# Sheet2.net
KiCad netlist of a schematic drawn in Altium Designer
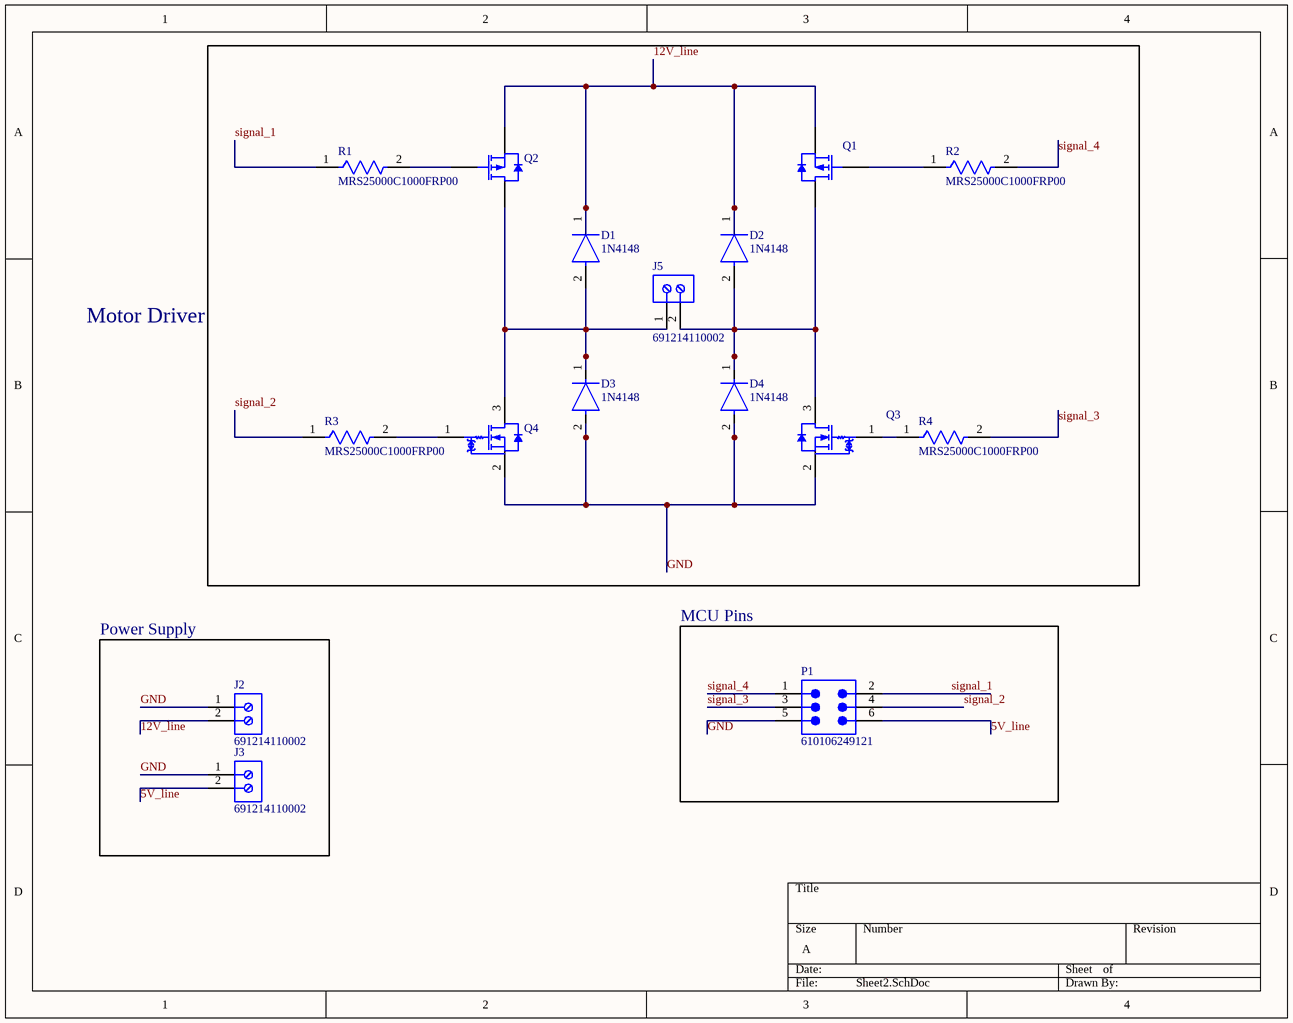
[diagram p0: Sheet2.SchDoc]

(export (version "E")
  (design (tool "Eeschema 10.0.6"))
  (components
    (comp (ref "D1")
      (value "1N4148")
      (footprint "FP-017AG-MFG")
      (description "DIODE GEN PURP 100V 200MA DO35")
      (fields (field (name "VOLTAGE") "100V"))
      (libsource (lib "Altium Content Vault") (part "d7152d700b627762746794eb795d46e"))
    )
    (comp (ref "D2")
      (value "1N4148")
      (footprint "FP-017AG-MFG")
      (description "DIODE GEN PURP 100V 200MA DO35")
      (fields (field (name "VOLTAGE") "100V"))
      (libsource (lib "Altium Content Vault") (part "d7152d700b627762746794eb795d46e"))
    )
    (comp (ref "D3")
      (value "1N4148")
      (footprint "FP-017AG-MFG")
      (description "DIODE GEN PURP 100V 200MA DO35")
      (fields (field (name "VOLTAGE") "100V"))
      (libsource (lib "Altium Content Vault") (part "d7152d700b627762746794eb795d46e"))
    )
    (comp (ref "D4")
      (value "1N4148")
      (footprint "FP-017AG-MFG")
      (description "DIODE GEN PURP 100V 200MA DO35")
      (fields (field (name "VOLTAGE") "100V"))
      (libsource (lib "Altium Content Vault") (part "d7152d700b627762746794eb795d46e"))
    )
    (comp (ref "J2")
      (value "691214110002")
      (footprint "691214110002")
      (fields (field (name "VOLTAGE") "300V"))
      (libsource (lib "Altium Content Vault") (part "TBL - 1R - 02P - Screw"))
    )
    (comp (ref "J3")
      (value "691214110002")
      (footprint "691214110002")
      (fields (field (name "VOLTAGE") "300V"))
      (libsource (lib "Altium Content Vault") (part "TBL - 1R - 02P - Screw"))
    )
    (comp (ref "J5")
      (value "691214110002")
      (footprint "691214110002")
      (fields (field (name "VOLTAGE") "300V"))
      (libsource (lib "Altium Content Vault") (part "TBL - 1R - 02P - Screw"))
    )
    (comp (ref "P1")
      (value "610106249121")
      (footprint "610106249121")
      (libsource (lib "Altium Content Vault") (part "Header_Male_2R_06P"))
    )
    (comp (ref "Q1")
      (value "SI2323DS-T1-E3")
      (footprint "VISH-SI2323DS-T1-E3-3_V")
      (description "P-Channel MOSFET, 20 V, -55 to 150 degC, 3-Pin TO-236, RoHS, Tape and Reel")
      (fields (field (name "MANUFACTURER") "Vishay"))
      (libsource (lib "Altium Content Vault") (part "VISH-SI2323DS-T1-E3-3"))
    )
    (comp (ref "Q2")
      (value "SI2323DS-T1-E3")
      (footprint "VISH-SI2323DS-T1-E3-3_V")
      (description "P-Channel MOSFET, 20 V, -55 to 150 degC, 3-Pin TO-236, RoHS, Tape and Reel")
      (fields (field (name "MANUFACTURER") "Vishay"))
      (libsource (lib "Altium Content Vault") (part "VISH-SI2323DS-T1-E3-3"))
    )
    (comp (ref "Q3")
      (value "2N7002WT1G")
      (footprint "ONSC-SC-70-3-419-04_V")
      (description "Small Signal MOSFET, 60 V, 340 mA, Single, N-Channel, 3-Pin SC70, Pb-Free, Tape and Reel")
      (fields (field (name "MANUFACTURER") "On Semiconductor"))
      (libsource (lib "Altium Content Vault") (part "ONSC-NMOS-G1S2D3-3_C"))
    )
    (comp (ref "Q4")
      (value "2N7002WT1G")
      (footprint "ONSC-SC-70-3-419-04_V")
      (description "Small Signal MOSFET, 60 V, 340 mA, Single, N-Channel, 3-Pin SC70, Pb-Free, Tape and Reel")
      (fields (field (name "MANUFACTURER") "On Semiconductor"))
      (libsource (lib "Altium Content Vault") (part "ONSC-NMOS-G1S2D3-3_C"))
    )
    (comp (ref "R1")
      (value "MRS25000C1000FRP00")
      (footprint "FP-MRS25-MFG")
      (fields (field (name "TOLERANCE") "1%"))
      (libsource (lib "Altium Content Vault") (part "1029c3af85768c4190bb7ad29bc67b5"))
    )
    (comp (ref "R2")
      (value "MRS25000C1000FRP00")
      (footprint "FP-MRS25-MFG")
      (fields (field (name "TOLERANCE") "1%"))
      (libsource (lib "Altium Content Vault") (part "1029c3af85768c4190bb7ad29bc67b5"))
    )
    (comp (ref "R3")
      (value "MRS25000C1000FRP00")
      (footprint "FP-MRS25-MFG")
      (fields (field (name "TOLERANCE") "1%"))
      (libsource (lib "Altium Content Vault") (part "1029c3af85768c4190bb7ad29bc67b5"))
    )
    (comp (ref "R4")
      (value "MRS25000C1000FRP00")
      (footprint "FP-MRS25-MFG")
      (fields (field (name "TOLERANCE") "1%"))
      (libsource (lib "Altium Content Vault") (part "1029c3af85768c4190bb7ad29bc67b5"))
    )
  )
  (nets
    (net (code "1") (name "/5V_line") (class "Default")
      (node (ref "J3") (pin "2") (pinfunction "2_2") (pintype "passive"))
      (node (ref "P1") (pin "6") (pinfunction "6_6") (pintype "passive"))
    )
    (net (code "2") (name "/12V_line") (class "Default")
      (node (ref "D1") (pin "1") (pinfunction "C_1") (pintype "passive"))
      (node (ref "D2") (pin "1") (pinfunction "C_1") (pintype "passive"))
      (node (ref "J2") (pin "2") (pinfunction "2_2") (pintype "passive"))
      (node (ref "Q1") (pin "2") (pinfunction "S_2") (pintype "passive"))
      (node (ref "Q2") (pin "2") (pinfunction "S_2") (pintype "passive"))
    )
    (net (code "3") (name "/GND") (class "Default")
      (node (ref "D3") (pin "2") (pinfunction "A_2") (pintype "passive"))
      (node (ref "D4") (pin "2") (pinfunction "A_2") (pintype "passive"))
      (node (ref "J2") (pin "1") (pinfunction "1_1") (pintype "passive"))
      (node (ref "J3") (pin "1") (pinfunction "1_1") (pintype "passive"))
      (node (ref "P1") (pin "5") (pinfunction "5_5") (pintype "passive"))
      (node (ref "Q3") (pin "2") (pinfunction "S_2") (pintype "passive"))
      (node (ref "Q4") (pin "2") (pinfunction "S_2") (pintype "passive"))
    )
    (net (code "4") (name "/signal_1") (class "Default")
      (node (ref "P1") (pin "2") (pinfunction "2_2") (pintype "passive"))
      (node (ref "R1") (pin "1") (pinfunction "1_1") (pintype "passive"))
    )
    (net (code "5") (name "/signal_2") (class "Default")
      (node (ref "P1") (pin "4") (pinfunction "4_4") (pintype "passive"))
      (node (ref "R3") (pin "1") (pinfunction "1_1") (pintype "passive"))
    )
    (net (code "6") (name "/signal_3") (class "Default")
      (node (ref "P1") (pin "3") (pinfunction "3_3") (pintype "passive"))
      (node (ref "R4") (pin "2") (pinfunction "2_2") (pintype "passive"))
    )
    (net (code "7") (name "/signal_4") (class "Default")
      (node (ref "P1") (pin "1") (pinfunction "1_1") (pintype "passive"))
      (node (ref "R2") (pin "2") (pinfunction "2_2") (pintype "passive"))
    )
    (net (code "8") (name "Net-(D1-A)") (class "Default")
      (node (ref "D1") (pin "2") (pinfunction "A_2") (pintype "passive"))
      (node (ref "D3") (pin "1") (pinfunction "C_1") (pintype "passive"))
      (node (ref "J5") (pin "1") (pinfunction "1_1") (pintype "passive"))
      (node (ref "Q2") (pin "3") (pinfunction "D_3") (pintype "passive"))
      (node (ref "Q4") (pin "3") (pinfunction "D_3") (pintype "passive"))
    )
    (net (code "9") (name "Net-(D2-A)") (class "Default")
      (node (ref "D2") (pin "2") (pinfunction "A_2") (pintype "passive"))
      (node (ref "D4") (pin "1") (pinfunction "C_1") (pintype "passive"))
      (node (ref "J5") (pin "2") (pinfunction "2_2") (pintype "passive"))
      (node (ref "Q1") (pin "3") (pinfunction "D_3") (pintype "passive"))
      (node (ref "Q3") (pin "3") (pinfunction "D_3") (pintype "passive"))
    )
    (net (code "10") (name "Net-(Q1-G)") (class "Default")
      (node (ref "Q1") (pin "1") (pinfunction "G_1") (pintype "passive"))
      (node (ref "R2") (pin "1") (pinfunction "1_1") (pintype "passive"))
    )
    (net (code "11") (name "Net-(Q2-G)") (class "Default")
      (node (ref "Q2") (pin "1") (pinfunction "G_1") (pintype "passive"))
      (node (ref "R1") (pin "2") (pinfunction "2_2") (pintype "passive"))
    )
    (net (code "12") (name "Net-(Q3-G)") (class "Default")
      (node (ref "Q3") (pin "1") (pinfunction "G_1") (pintype "passive"))
      (node (ref "R4") (pin "1") (pinfunction "1_1") (pintype "passive"))
    )
    (net (code "13") (name "Net-(Q4-G)") (class "Default")
      (node (ref "Q4") (pin "1") (pinfunction "G_1") (pintype "passive"))
      (node (ref "R3") (pin "2") (pinfunction "2_2") (pintype "passive"))
    )
  )
)
